# LocIT.net
KiCad netlist of a schematic drawn in EAGLE
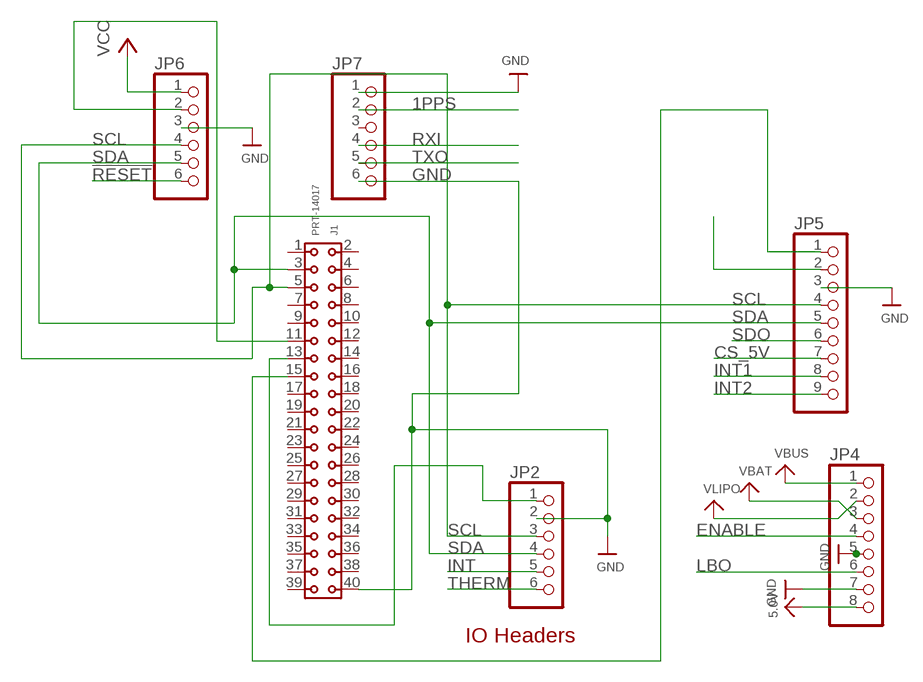
[diagram p0: schematic, sheet 1]

(export (version "E")
  (design (tool "Eeschema 10.0.6"))
  (components
    (comp (ref "J1")
      (value "PRT-14017")
      (footprint "eagle-import:61304021821")
      (fields (field (name "MF") "SparkFun Electronics"))
      (libsource (lib "eagle-import") (part "PRT-14017"))
    )
    (comp (ref "JP2")
      (value "HEADER-1X670MIL")
      (footprint "eagle-import:1X06_ROUND_70")
      (libsource (lib "eagle-import") (part "HEADER-1X670MIL"))
    )
    (comp (ref "JP4")
      (value "HEADER-1X8ROUND")
      (footprint "eagle-import:1X08_ROUND")
      (libsource (lib "eagle-import") (part "HEADER-1X8ROUND"))
    )
    (comp (ref "JP5")
      (value "HEADER-1X970MIL")
      (footprint "eagle-import:1X09_ROUND_70")
      (libsource (lib "eagle-import") (part "HEADER-1X970MIL"))
    )
    (comp (ref "JP6")
      (value "HEADER-1X670MIL")
      (footprint "eagle-import:1X06_ROUND_70")
      (libsource (lib "eagle-import") (part "HEADER-1X670MIL"))
    )
    (comp (ref "JP7")
      (value "HEADER-1X670MIL")
      (footprint "eagle-import:1X06_ROUND_70")
      (libsource (lib "eagle-import") (part "HEADER-1X670MIL"))
    )
  )
  (nets
    (net (code "1") (name "/1PPS") (class "Default")
      (node (ref "JP7") (pin "2") (pinfunction "2_2") (pintype "passive"))
    )
    (net (code "2") (name "/CS_5V") (class "Default")
      (node (ref "JP5") (pin "7") (pinfunction "7_7") (pintype "passive"))
    )
    (net (code "3") (name "/ENABLE") (class "Default")
      (node (ref "JP4") (pin "4") (pinfunction "4_4") (pintype "passive"))
    )
    (net (code "4") (name "/INT") (class "Default")
      (node (ref "JP2") (pin "5") (pinfunction "5_5") (pintype "passive"))
    )
    (net (code "5") (name "/INT1") (class "Default")
      (node (ref "JP5") (pin "8") (pinfunction "8_8") (pintype "passive"))
    )
    (net (code "6") (name "/INT2") (class "Default")
      (node (ref "JP5") (pin "9") (pinfunction "9_9") (pintype "passive"))
    )
    (net (code "7") (name "/LBO") (class "Default")
      (node (ref "JP4") (pin "6") (pinfunction "6_6") (pintype "passive"))
    )
    (net (code "8") (name "/RXI") (class "Default")
      (node (ref "JP7") (pin "4") (pinfunction "4_4") (pintype "passive"))
    )
    (net (code "9") (name "/SCL") (class "Default")
      (node (ref "J1") (pin "5") (pinfunction "5_5") (pintype "passive"))
      (node (ref "JP2") (pin "3") (pinfunction "3_3") (pintype "passive"))
      (node (ref "JP5") (pin "4") (pinfunction "4_4") (pintype "passive"))
      (node (ref "JP6") (pin "4") (pinfunction "4_4") (pintype "passive"))
    )
    (net (code "10") (name "/SDA") (class "Default")
      (node (ref "J1") (pin "3") (pinfunction "3_3") (pintype "passive"))
      (node (ref "JP2") (pin "4") (pinfunction "4_4") (pintype "passive"))
      (node (ref "JP5") (pin "5") (pinfunction "5_5") (pintype "passive"))
      (node (ref "JP6") (pin "5") (pinfunction "5_5") (pintype "passive"))
    )
    (net (code "11") (name "/SDO") (class "Default")
      (node (ref "JP5") (pin "6") (pinfunction "6_6") (pintype "passive"))
    )
    (net (code "12") (name "/THERM") (class "Default")
      (node (ref "JP2") (pin "6") (pinfunction "6_6") (pintype "passive"))
    )
    (net (code "13") (name "/TXO") (class "Default")
      (node (ref "JP7") (pin "5") (pinfunction "5_5") (pintype "passive"))
    )
    (net (code "14") (name "/~{RESET}") (class "Default")
      (node (ref "JP6") (pin "6") (pinfunction "6_6") (pintype "passive"))
    )
    (net (code "15") (name "5.0V") (class "Default")
      (node (ref "JP4") (pin "8") (pinfunction "8_8") (pintype "passive"))
    )
    (net (code "16") (name "GND") (class "Default")
      (node (ref "J1") (pin "40") (pinfunction "40_40") (pintype "passive"))
      (node (ref "JP2") (pin "2") (pinfunction "2_2") (pintype "passive"))
      (node (ref "JP4") (pin "5") (pinfunction "5_5") (pintype "passive"))
      (node (ref "JP4") (pin "7") (pinfunction "7_7") (pintype "passive"))
      (node (ref "JP5") (pin "3") (pinfunction "3_3") (pintype "passive"))
      (node (ref "JP6") (pin "3") (pinfunction "3_3") (pintype "passive"))
      (node (ref "JP7") (pin "1") (pinfunction "1_1") (pintype "passive"))
      (node (ref "JP7") (pin "6") (pinfunction "6_6") (pintype "passive"))
    )
    (net (code "17") (name "Net-(J1-Pad11)") (class "Default")
      (node (ref "J1") (pin "11") (pinfunction "11_11") (pintype "passive"))
      (node (ref "JP6") (pin "2") (pinfunction "2_2") (pintype "passive"))
    )
    (net (code "18") (name "Net-(J1-Pad13)") (class "Default")
      (node (ref "J1") (pin "13") (pinfunction "13_13") (pintype "passive"))
      (node (ref "JP2") (pin "1") (pinfunction "1_1") (pintype "passive"))
    )
    (net (code "19") (name "Net-(J1-Pad15)") (class "Default")
      (node (ref "J1") (pin "15") (pinfunction "15_15") (pintype "passive"))
      (node (ref "JP5") (pin "1") (pinfunction "1_1") (pintype "passive"))
    )
    (net (code "20") (name "VBAT") (class "Default")
      (node (ref "JP4") (pin "3") (pinfunction "3_3") (pintype "passive"))
    )
    (net (code "21") (name "VBUS") (class "Default")
      (node (ref "JP4") (pin "1") (pinfunction "1_1") (pintype "passive"))
    )
    (net (code "22") (name "VCC") (class "Default")
      (node (ref "JP6") (pin "1") (pinfunction "1_1") (pintype "passive"))
    )
    (net (code "23") (name "VLIPO") (class "Default")
      (node (ref "JP4") (pin "2") (pinfunction "2_2") (pintype "passive"))
    )
    (net (code "24") (name "unconnected-(J1-Pad1)") (class "Default")
      (node (ref "J1") (pin "1") (pinfunction "1_1") (pintype "passive"))
    )
    (net (code "25") (name "unconnected-(J1-Pad2)") (class "Default")
      (node (ref "J1") (pin "2") (pinfunction "2_2") (pintype "passive"))
    )
    (net (code "26") (name "unconnected-(J1-Pad4)") (class "Default")
      (node (ref "J1") (pin "4") (pinfunction "4_4") (pintype "passive"))
    )
    (net (code "27") (name "unconnected-(J1-Pad6)") (class "Default")
      (node (ref "J1") (pin "6") (pinfunction "6_6") (pintype "passive"))
    )
    (net (code "28") (name "unconnected-(J1-Pad7)") (class "Default")
      (node (ref "J1") (pin "7") (pinfunction "7_7") (pintype "passive"))
    )
    (net (code "29") (name "unconnected-(J1-Pad8)") (class "Default")
      (node (ref "J1") (pin "8") (pinfunction "8_8") (pintype "passive"))
    )
    (net (code "30") (name "unconnected-(J1-Pad9)") (class "Default")
      (node (ref "J1") (pin "9") (pinfunction "9_9") (pintype "passive"))
    )
    (net (code "31") (name "unconnected-(J1-Pad10)") (class "Default")
      (node (ref "J1") (pin "10") (pinfunction "10_10") (pintype "passive"))
    )
    (net (code "32") (name "unconnected-(J1-Pad12)") (class "Default")
      (node (ref "J1") (pin "12") (pinfunction "12_12") (pintype "passive"))
    )
    (net (code "33") (name "unconnected-(J1-Pad14)") (class "Default")
      (node (ref "J1") (pin "14") (pinfunction "14_14") (pintype "passive"))
    )
    (net (code "34") (name "unconnected-(J1-Pad16)") (class "Default")
      (node (ref "J1") (pin "16") (pinfunction "16_16") (pintype "passive"))
    )
    (net (code "35") (name "unconnected-(J1-Pad17)") (class "Default")
      (node (ref "J1") (pin "17") (pinfunction "17_17") (pintype "passive"))
    )
    (net (code "36") (name "unconnected-(J1-Pad18)") (class "Default")
      (node (ref "J1") (pin "18") (pinfunction "18_18") (pintype "passive"))
    )
    (net (code "37") (name "unconnected-(J1-Pad19)") (class "Default")
      (node (ref "J1") (pin "19") (pinfunction "19_19") (pintype "passive"))
    )
    (net (code "38") (name "unconnected-(J1-Pad20)") (class "Default")
      (node (ref "J1") (pin "20") (pinfunction "20_20") (pintype "passive"))
    )
    (net (code "39") (name "unconnected-(J1-Pad21)") (class "Default")
      (node (ref "J1") (pin "21") (pinfunction "21_21") (pintype "passive"))
    )
    (net (code "40") (name "unconnected-(J1-Pad22)") (class "Default")
      (node (ref "J1") (pin "22") (pinfunction "22_22") (pintype "passive"))
    )
    (net (code "41") (name "unconnected-(J1-Pad23)") (class "Default")
      (node (ref "J1") (pin "23") (pinfunction "23_23") (pintype "passive"))
    )
    (net (code "42") (name "unconnected-(J1-Pad24)") (class "Default")
      (node (ref "J1") (pin "24") (pinfunction "24_24") (pintype "passive"))
    )
    (net (code "43") (name "unconnected-(J1-Pad25)") (class "Default")
      (node (ref "J1") (pin "25") (pinfunction "25_25") (pintype "passive"))
    )
    (net (code "44") (name "unconnected-(J1-Pad26)") (class "Default")
      (node (ref "J1") (pin "26") (pinfunction "26_26") (pintype "passive"))
    )
    (net (code "45") (name "unconnected-(J1-Pad27)") (class "Default")
      (node (ref "J1") (pin "27") (pinfunction "27_27") (pintype "passive"))
    )
    (net (code "46") (name "unconnected-(J1-Pad28)") (class "Default")
      (node (ref "J1") (pin "28") (pinfunction "28_28") (pintype "passive"))
    )
    (net (code "47") (name "unconnected-(J1-Pad29)") (class "Default")
      (node (ref "J1") (pin "29") (pinfunction "29_29") (pintype "passive"))
    )
    (net (code "48") (name "unconnected-(J1-Pad30)") (class "Default")
      (node (ref "J1") (pin "30") (pinfunction "30_30") (pintype "passive"))
    )
    (net (code "49") (name "unconnected-(J1-Pad31)") (class "Default")
      (node (ref "J1") (pin "31") (pinfunction "31_31") (pintype "passive"))
    )
    (net (code "50") (name "unconnected-(J1-Pad32)") (class "Default")
      (node (ref "J1") (pin "32") (pinfunction "32_32") (pintype "passive"))
    )
    (net (code "51") (name "unconnected-(J1-Pad33)") (class "Default")
      (node (ref "J1") (pin "33") (pinfunction "33_33") (pintype "passive"))
    )
    (net (code "52") (name "unconnected-(J1-Pad34)") (class "Default")
      (node (ref "J1") (pin "34") (pinfunction "34_34") (pintype "passive"))
    )
    (net (code "53") (name "unconnected-(J1-Pad35)") (class "Default")
      (node (ref "J1") (pin "35") (pinfunction "35_35") (pintype "passive"))
    )
    (net (code "54") (name "unconnected-(J1-Pad36)") (class "Default")
      (node (ref "J1") (pin "36") (pinfunction "36_36") (pintype "passive"))
    )
    (net (code "55") (name "unconnected-(J1-Pad37)") (class "Default")
      (node (ref "J1") (pin "37") (pinfunction "37_37") (pintype "passive"))
    )
    (net (code "56") (name "unconnected-(J1-Pad38)") (class "Default")
      (node (ref "J1") (pin "38") (pinfunction "38_38") (pintype "passive"))
    )
    (net (code "57") (name "unconnected-(J1-Pad39)") (class "Default")
      (node (ref "J1") (pin "39") (pinfunction "39_39") (pintype "passive"))
    )
    (net (code "58") (name "unconnected-(JP5-Pad2)") (class "Default")
      (node (ref "JP5") (pin "2") (pinfunction "2_2") (pintype "passive"))
    )
    (net (code "59") (name "unconnected-(JP7-Pad3)") (class "Default")
      (node (ref "JP7") (pin "3") (pinfunction "3_3") (pintype "passive"))
    )
  )
)
